# Sunfish_ECU_MotorDriver_RevA.net
KiCad netlist of a schematic drawn in Altium Designer
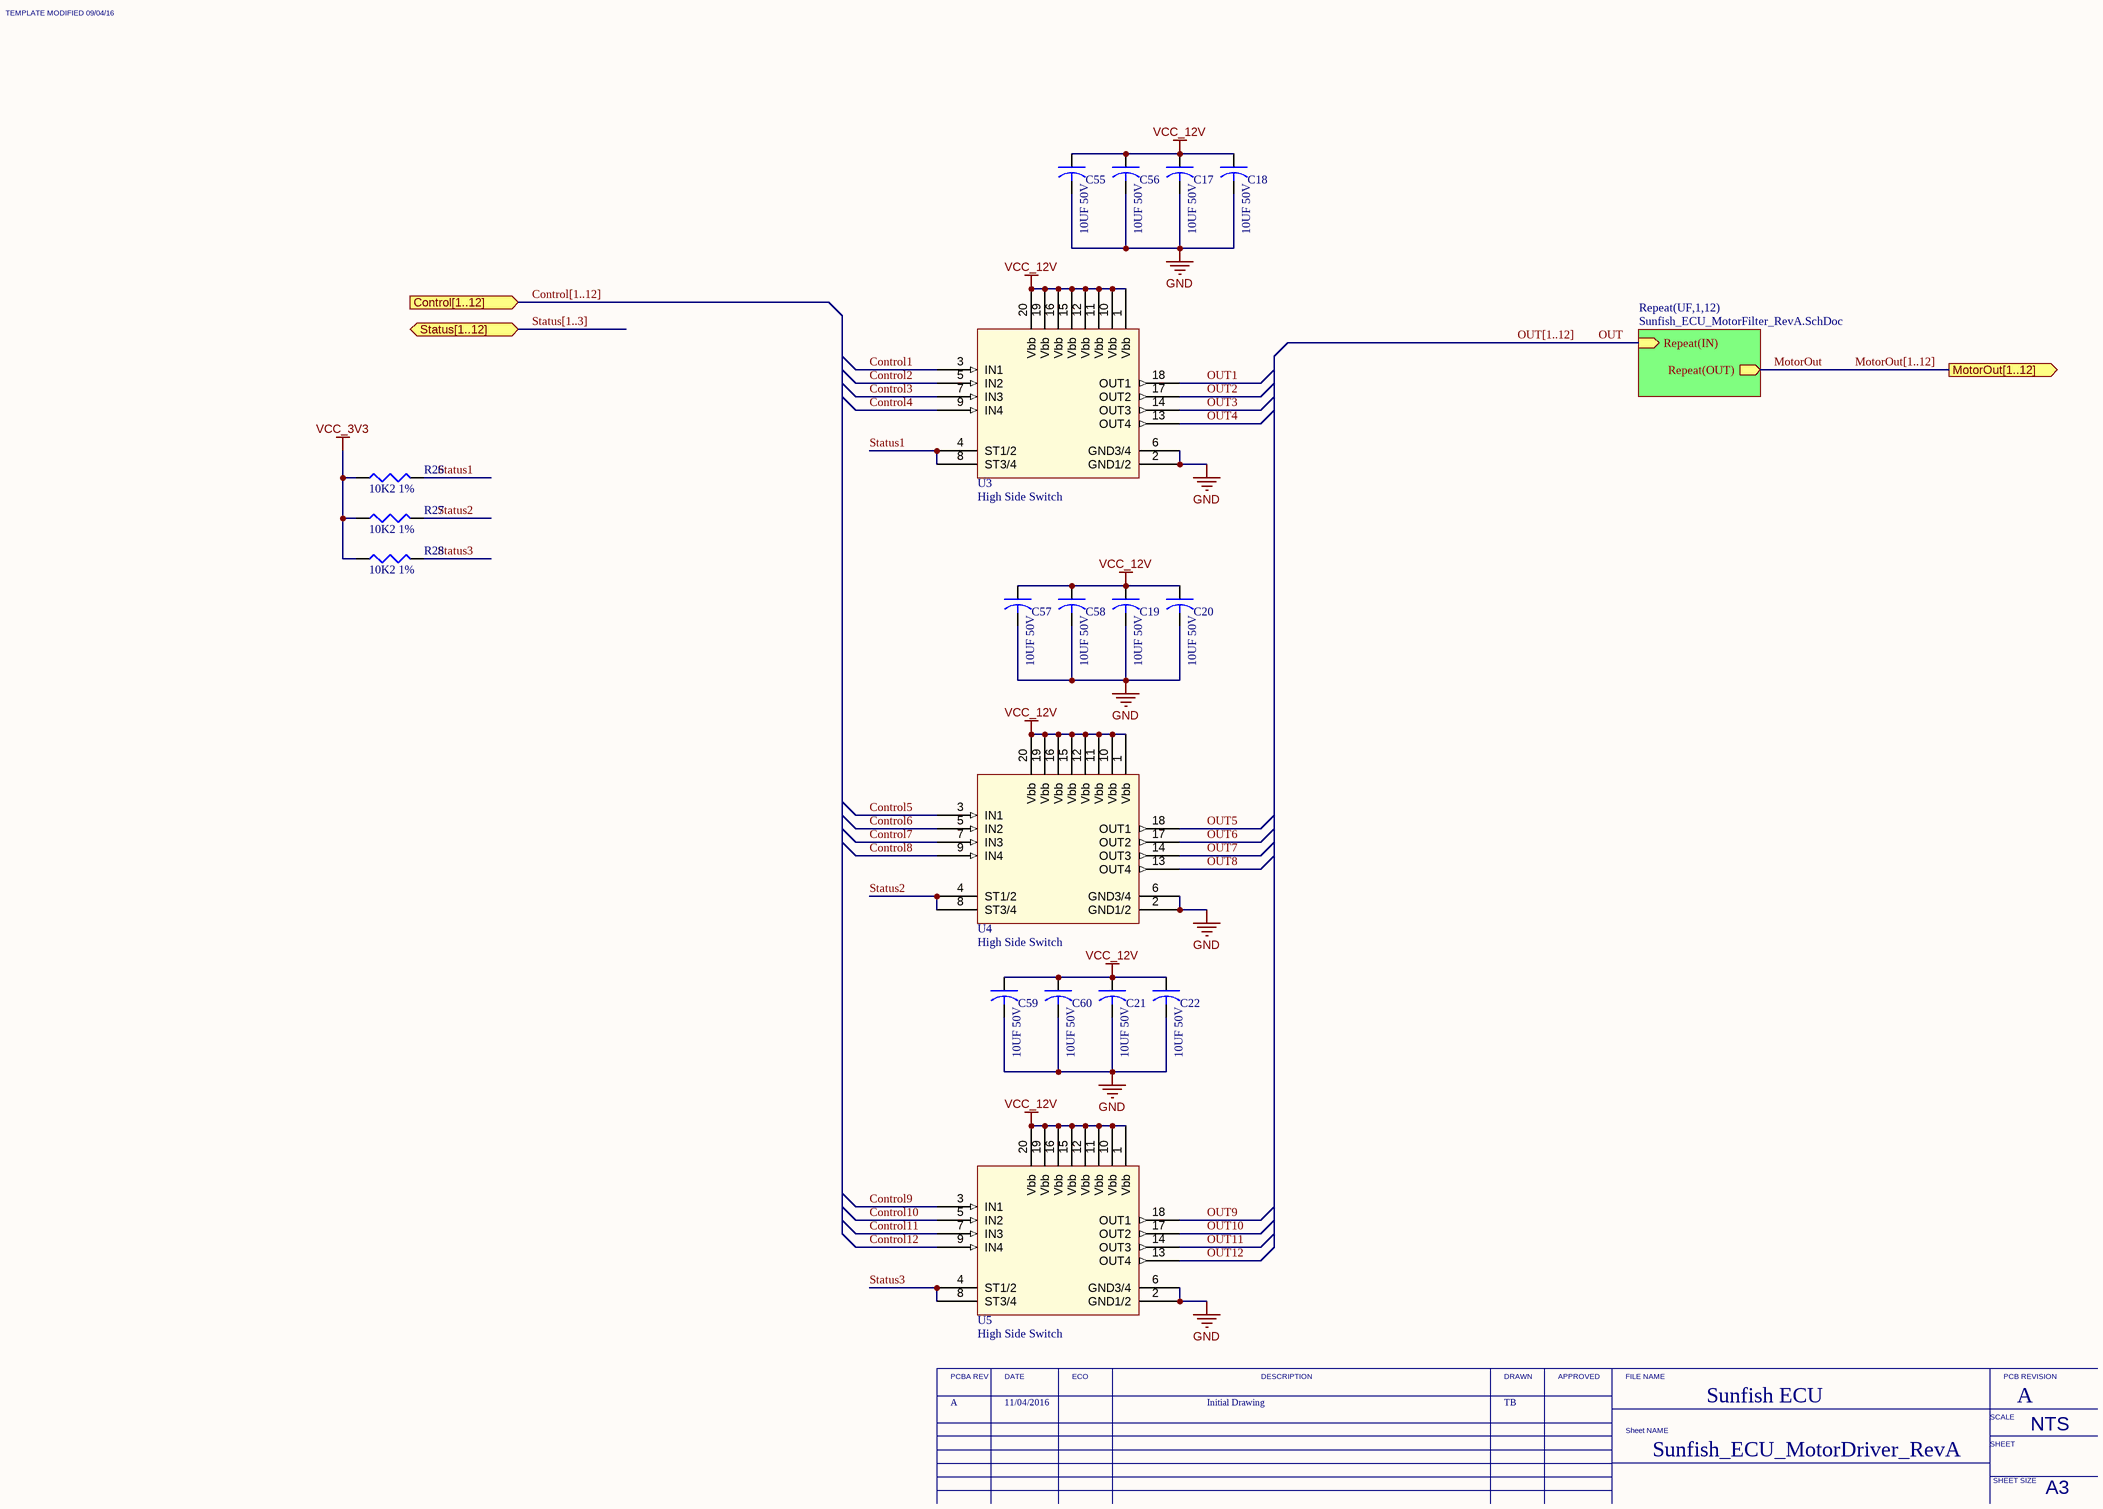
[diagram p0: Sunfish_ECU_MotorDriver_RevA.SchDoc]

(export (version "E")
  (design (tool "Eeschema 10.0.6"))
  (components
    (comp (ref "C17")
      (value "10UF 50V")
      (footprint "1206")
      (description "CAP CER 10UF 50V 10% X5R 1206")
      (fields (field (name "MANUFACTURER") "Murata"))
      (libsource (lib "Regulators") (part "CAP_10UF_50V_10%_1206"))
    )
    (comp (ref "C18")
      (value "10UF 50V")
      (footprint "1206")
      (description "CAP CER 10UF 50V 10% X5R 1206")
      (fields (field (name "MANUFACTURER") "Murata"))
      (libsource (lib "Regulators") (part "CAP_10UF_50V_10%_1206"))
    )
    (comp (ref "C19")
      (value "10UF 50V")
      (footprint "1206")
      (description "CAP CER 10UF 50V 10% X5R 1206")
      (fields (field (name "MANUFACTURER") "Murata"))
      (libsource (lib "Regulators") (part "CAP_10UF_50V_10%_1206"))
    )
    (comp (ref "C20")
      (value "10UF 50V")
      (footprint "1206")
      (description "CAP CER 10UF 50V 10% X5R 1206")
      (fields (field (name "MANUFACTURER") "Murata"))
      (libsource (lib "Regulators") (part "CAP_10UF_50V_10%_1206"))
    )
    (comp (ref "C21")
      (value "10UF 50V")
      (footprint "1206")
      (description "CAP CER 10UF 50V 10% X5R 1206")
      (fields (field (name "MANUFACTURER") "Murata"))
      (libsource (lib "Regulators") (part "CAP_10UF_50V_10%_1206"))
    )
    (comp (ref "C22")
      (value "10UF 50V")
      (footprint "1206")
      (description "CAP CER 10UF 50V 10% X5R 1206")
      (fields (field (name "MANUFACTURER") "Murata"))
      (libsource (lib "Regulators") (part "CAP_10UF_50V_10%_1206"))
    )
    (comp (ref "C55")
      (value "10UF 50V")
      (footprint "1206")
      (description "CAP CER 10UF 50V 10% X5R 1206")
      (fields (field (name "MANUFACTURER") "Murata"))
      (libsource (lib "Regulators") (part "CAP_10UF_50V_10%_1206"))
    )
    (comp (ref "C56")
      (value "10UF 50V")
      (footprint "1206")
      (description "CAP CER 10UF 50V 10% X5R 1206")
      (fields (field (name "MANUFACTURER") "Murata"))
      (libsource (lib "Regulators") (part "CAP_10UF_50V_10%_1206"))
    )
    (comp (ref "C57")
      (value "10UF 50V")
      (footprint "1206")
      (description "CAP CER 10UF 50V 10% X5R 1206")
      (fields (field (name "MANUFACTURER") "Murata"))
      (libsource (lib "Regulators") (part "CAP_10UF_50V_10%_1206"))
    )
    (comp (ref "C58")
      (value "10UF 50V")
      (footprint "1206")
      (description "CAP CER 10UF 50V 10% X5R 1206")
      (fields (field (name "MANUFACTURER") "Murata"))
      (libsource (lib "Regulators") (part "CAP_10UF_50V_10%_1206"))
    )
    (comp (ref "C59")
      (value "10UF 50V")
      (footprint "1206")
      (description "CAP CER 10UF 50V 10% X5R 1206")
      (fields (field (name "MANUFACTURER") "Murata"))
      (libsource (lib "Regulators") (part "CAP_10UF_50V_10%_1206"))
    )
    (comp (ref "C60")
      (value "10UF 50V")
      (footprint "1206")
      (description "CAP CER 10UF 50V 10% X5R 1206")
      (fields (field (name "MANUFACTURER") "Murata"))
      (libsource (lib "Regulators") (part "CAP_10UF_50V_10%_1206"))
    )
    (comp (ref "R26")
      (value "10K2 1%")
      (footprint "0603")
      (description "Resistor, 10K2, 1%, 0603")
      (fields (field (name "MANUFACTURER") "Yageo"))
      (libsource (lib "Resistors") (part "RES_10K2_1%_0603"))
    )
    (comp (ref "R27")
      (value "10K2 1%")
      (footprint "0603")
      (description "Resistor, 10K2, 1%, 0603")
      (fields (field (name "MANUFACTURER") "Yageo"))
      (libsource (lib "Resistors") (part "RES_10K2_1%_0603"))
    )
    (comp (ref "R28")
      (value "10K2 1%")
      (footprint "0603")
      (description "Resistor, 10K2, 1%, 0603")
      (fields (field (name "MANUFACTURER") "Yageo"))
      (libsource (lib "Resistors") (part "RES_10K2_1%_0603"))
    )
    (comp (ref "U3")
      (value "High Side Switch")
      (footprint "SOIC127P1030X265-20M")
      (description "IC HISIDE PWR SWITCH 4CH PDSO-20")
      (fields (field (name "MANUFACTURER") "Infineon"))
      (libsource (lib "IC") (part "IC_HSS_BTS724G"))
    )
    (comp (ref "U4")
      (value "High Side Switch")
      (footprint "SOIC127P1030X265-20M")
      (description "IC HISIDE PWR SWITCH 4CH PDSO-20")
      (fields (field (name "MANUFACTURER") "Infineon"))
      (libsource (lib "IC") (part "IC_HSS_BTS724G"))
    )
    (comp (ref "U5")
      (value "High Side Switch")
      (footprint "SOIC127P1030X265-20M")
      (description "IC HISIDE PWR SWITCH 4CH PDSO-20")
      (fields (field (name "MANUFACTURER") "Infineon"))
      (libsource (lib "IC") (part "IC_HSS_BTS724G"))
    )
  )
  (nets
    (net (code "13") (name "/Control1") (class "Default")
      (node (ref "U3") (pin "3") (pinfunction "IN1_3") (pintype "input"))
    )
    (net (code "14") (name "/Control2") (class "Default")
      (node (ref "U3") (pin "5") (pinfunction "IN2_5") (pintype "input"))
    )
    (net (code "15") (name "/Control3") (class "Default")
      (node (ref "U3") (pin "7") (pinfunction "IN3_7") (pintype "input"))
    )
    (net (code "16") (name "/Control4") (class "Default")
      (node (ref "U3") (pin "9") (pinfunction "IN4_9") (pintype "input"))
    )
    (net (code "17") (name "/Control5") (class "Default")
      (node (ref "U4") (pin "3") (pinfunction "IN1_3") (pintype "input"))
    )
    (net (code "18") (name "/Control6") (class "Default")
      (node (ref "U4") (pin "5") (pinfunction "IN2_5") (pintype "input"))
    )
    (net (code "19") (name "/Control7") (class "Default")
      (node (ref "U4") (pin "7") (pinfunction "IN3_7") (pintype "input"))
    )
    (net (code "20") (name "/Control8") (class "Default")
      (node (ref "U4") (pin "9") (pinfunction "IN4_9") (pintype "input"))
    )
    (net (code "21") (name "/Control9") (class "Default")
      (node (ref "U5") (pin "3") (pinfunction "IN1_3") (pintype "input"))
    )
    (net (code "22") (name "/Control10") (class "Default")
      (node (ref "U5") (pin "5") (pinfunction "IN2_5") (pintype "input"))
    )
    (net (code "23") (name "/Control11") (class "Default")
      (node (ref "U5") (pin "7") (pinfunction "IN3_7") (pintype "input"))
    )
    (net (code "24") (name "/Control12") (class "Default")
      (node (ref "U5") (pin "9") (pinfunction "IN4_9") (pintype "input"))
    )
    (net (code "29") (name "/OUT1") (class "Default")
      (node (ref "U3") (pin "18") (pinfunction "OUT1_18") (pintype "output"))
    )
    (net (code "30") (name "/OUT2") (class "Default")
      (node (ref "U3") (pin "17") (pinfunction "OUT2_17") (pintype "output"))
    )
    (net (code "31") (name "/OUT3") (class "Default")
      (node (ref "U3") (pin "14") (pinfunction "OUT3_14") (pintype "output"))
    )
    (net (code "32") (name "/OUT4") (class "Default")
      (node (ref "U3") (pin "13") (pinfunction "OUT4_13") (pintype "output"))
    )
    (net (code "33") (name "/OUT5") (class "Default")
      (node (ref "U4") (pin "18") (pinfunction "OUT1_18") (pintype "output"))
    )
    (net (code "34") (name "/OUT6") (class "Default")
      (node (ref "U4") (pin "17") (pinfunction "OUT2_17") (pintype "output"))
    )
    (net (code "35") (name "/OUT7") (class "Default")
      (node (ref "U4") (pin "14") (pinfunction "OUT3_14") (pintype "output"))
    )
    (net (code "36") (name "/OUT8") (class "Default")
      (node (ref "U4") (pin "13") (pinfunction "OUT4_13") (pintype "output"))
    )
    (net (code "37") (name "/OUT9") (class "Default")
      (node (ref "U5") (pin "18") (pinfunction "OUT1_18") (pintype "output"))
    )
    (net (code "38") (name "/OUT10") (class "Default")
      (node (ref "U5") (pin "17") (pinfunction "OUT2_17") (pintype "output"))
    )
    (net (code "39") (name "/OUT11") (class "Default")
      (node (ref "U5") (pin "14") (pinfunction "OUT3_14") (pintype "output"))
    )
    (net (code "40") (name "/OUT12") (class "Default")
      (node (ref "U5") (pin "13") (pinfunction "OUT4_13") (pintype "output"))
    )
    (net (code "42") (name "/Status1") (class "Default")
      (node (ref "R26") (pin "2") (pintype "passive"))
      (node (ref "U3") (pin "4") (pinfunction "ST1/2_4") (pintype "open_collector"))
      (node (ref "U3") (pin "8") (pinfunction "ST3/4_8") (pintype "open_collector"))
    )
    (net (code "43") (name "/Status2") (class "Default")
      (node (ref "R27") (pin "2") (pintype "passive"))
      (node (ref "U4") (pin "4") (pinfunction "ST1/2_4") (pintype "open_collector"))
      (node (ref "U4") (pin "8") (pinfunction "ST3/4_8") (pintype "open_collector"))
    )
    (net (code "44") (name "/Status3") (class "Default")
      (node (ref "R28") (pin "2") (pintype "passive"))
      (node (ref "U5") (pin "4") (pinfunction "ST1/2_4") (pintype "open_collector"))
      (node (ref "U5") (pin "8") (pinfunction "ST3/4_8") (pintype "open_collector"))
    )
    (net (code "46") (name "GND") (class "Default")
      (node (ref "C17") (pin "2") (pinfunction "2_2") (pintype "passive"))
      (node (ref "C18") (pin "2") (pinfunction "2_2") (pintype "passive"))
      (node (ref "C19") (pin "2") (pinfunction "2_2") (pintype "passive"))
      (node (ref "C20") (pin "2") (pinfunction "2_2") (pintype "passive"))
      (node (ref "C21") (pin "2") (pinfunction "2_2") (pintype "passive"))
      (node (ref "C22") (pin "2") (pinfunction "2_2") (pintype "passive"))
      (node (ref "C55") (pin "2") (pinfunction "2_2") (pintype "passive"))
      (node (ref "C56") (pin "2") (pinfunction "2_2") (pintype "passive"))
      (node (ref "C57") (pin "2") (pinfunction "2_2") (pintype "passive"))
      (node (ref "C58") (pin "2") (pinfunction "2_2") (pintype "passive"))
      (node (ref "C59") (pin "2") (pinfunction "2_2") (pintype "passive"))
      (node (ref "C60") (pin "2") (pinfunction "2_2") (pintype "passive"))
      (node (ref "U3") (pin "2") (pinfunction "GND1/2_2") (pintype "power_in"))
      (node (ref "U3") (pin "6") (pinfunction "GND3/4_6") (pintype "power_in"))
      (node (ref "U4") (pin "2") (pinfunction "GND1/2_2") (pintype "power_in"))
      (node (ref "U4") (pin "6") (pinfunction "GND3/4_6") (pintype "power_in"))
      (node (ref "U5") (pin "2") (pinfunction "GND1/2_2") (pintype "power_in"))
      (node (ref "U5") (pin "6") (pinfunction "GND3/4_6") (pintype "power_in"))
    )
    (net (code "47") (name "VCC_3V3") (class "Default")
      (node (ref "R26") (pin "1") (pintype "passive"))
      (node (ref "R27") (pin "1") (pintype "passive"))
      (node (ref "R28") (pin "1") (pintype "passive"))
    )
    (net (code "48") (name "VCC_12V") (class "Default")
      (node (ref "C17") (pin "1") (pinfunction "1_1") (pintype "passive"))
      (node (ref "C18") (pin "1") (pinfunction "1_1") (pintype "passive"))
      (node (ref "C19") (pin "1") (pinfunction "1_1") (pintype "passive"))
      (node (ref "C20") (pin "1") (pinfunction "1_1") (pintype "passive"))
      (node (ref "C21") (pin "1") (pinfunction "1_1") (pintype "passive"))
      (node (ref "C22") (pin "1") (pinfunction "1_1") (pintype "passive"))
      (node (ref "C55") (pin "1") (pinfunction "1_1") (pintype "passive"))
      (node (ref "C56") (pin "1") (pinfunction "1_1") (pintype "passive"))
      (node (ref "C57") (pin "1") (pinfunction "1_1") (pintype "passive"))
      (node (ref "C58") (pin "1") (pinfunction "1_1") (pintype "passive"))
      (node (ref "C59") (pin "1") (pinfunction "1_1") (pintype "passive"))
      (node (ref "C60") (pin "1") (pinfunction "1_1") (pintype "passive"))
      (node (ref "U3") (pin "1") (pinfunction "Vbb_1") (pintype "power_in"))
      (node (ref "U3") (pin "10") (pinfunction "Vbb_10") (pintype "power_in"))
      (node (ref "U3") (pin "11") (pinfunction "Vbb_11") (pintype "power_in"))
      (node (ref "U3") (pin "12") (pinfunction "Vbb_12") (pintype "power_in"))
      (node (ref "U3") (pin "15") (pinfunction "Vbb_15") (pintype "power_in"))
      (node (ref "U3") (pin "16") (pinfunction "Vbb_16") (pintype "power_in"))
      (node (ref "U3") (pin "19") (pinfunction "Vbb_19") (pintype "power_in"))
      (node (ref "U3") (pin "20") (pinfunction "Vbb_20") (pintype "power_in"))
      (node (ref "U4") (pin "1") (pinfunction "Vbb_1") (pintype "power_in"))
      (node (ref "U4") (pin "10") (pinfunction "Vbb_10") (pintype "power_in"))
      (node (ref "U4") (pin "11") (pinfunction "Vbb_11") (pintype "power_in"))
      (node (ref "U4") (pin "12") (pinfunction "Vbb_12") (pintype "power_in"))
      (node (ref "U4") (pin "15") (pinfunction "Vbb_15") (pintype "power_in"))
      (node (ref "U4") (pin "16") (pinfunction "Vbb_16") (pintype "power_in"))
      (node (ref "U4") (pin "19") (pinfunction "Vbb_19") (pintype "power_in"))
      (node (ref "U4") (pin "20") (pinfunction "Vbb_20") (pintype "power_in"))
      (node (ref "U5") (pin "1") (pinfunction "Vbb_1") (pintype "power_in"))
      (node (ref "U5") (pin "10") (pinfunction "Vbb_10") (pintype "power_in"))
      (node (ref "U5") (pin "11") (pinfunction "Vbb_11") (pintype "power_in"))
      (node (ref "U5") (pin "12") (pinfunction "Vbb_12") (pintype "power_in"))
      (node (ref "U5") (pin "15") (pinfunction "Vbb_15") (pintype "power_in"))
      (node (ref "U5") (pin "16") (pinfunction "Vbb_16") (pintype "power_in"))
      (node (ref "U5") (pin "19") (pinfunction "Vbb_19") (pintype "power_in"))
      (node (ref "U5") (pin "20") (pinfunction "Vbb_20") (pintype "power_in"))
    )
  )
)
